# ahe_v1_0.net
KiCad netlist of a schematic drawn in EAGLE
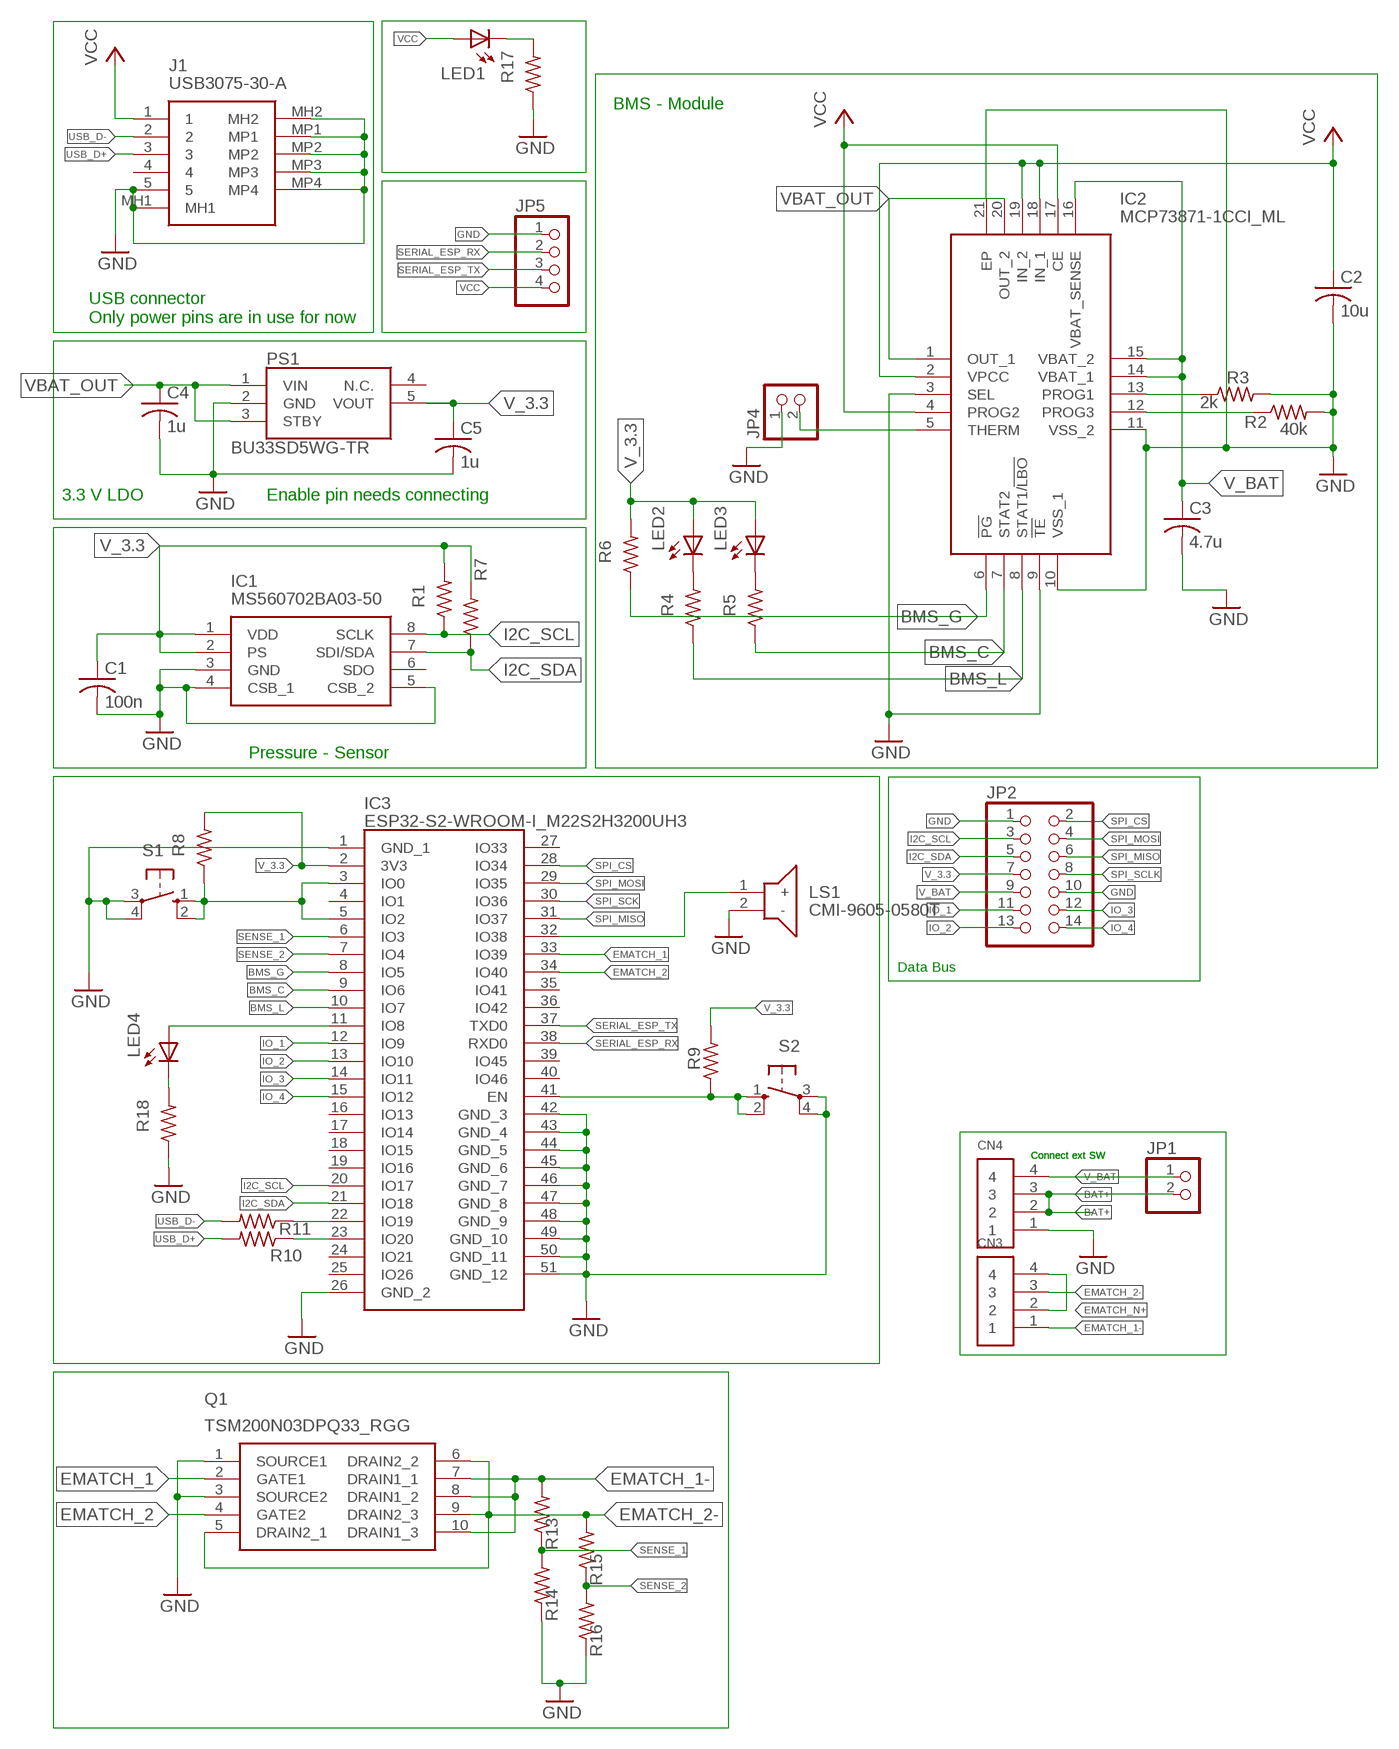
[diagram p0: schematic, sheet 1]

(export (version "E")
  (design (tool "Eeschema 10.0.6"))
  (components
    (comp (ref "C1")
      (value "100n")
      (footprint "eagle-import:C0805")
      (libsource (lib "eagle-import") (part "C-USC0805"))
    )
    (comp (ref "C2")
      (value "10u")
      (footprint "eagle-import:C0805")
      (libsource (lib "eagle-import") (part "C-USC0805"))
    )
    (comp (ref "C3")
      (value "4.7u")
      (footprint "eagle-import:C0805")
      (libsource (lib "eagle-import") (part "C-USC0805"))
    )
    (comp (ref "C4")
      (value "1u")
      (footprint "eagle-import:C0805")
      (libsource (lib "eagle-import") (part "C-USC0805"))
    )
    (comp (ref "C5")
      (value "1u")
      (footprint "eagle-import:C0805")
      (libsource (lib "eagle-import") (part "C-USC0805"))
    )
    (comp (ref "CN3")
      (value "1X4-3.5MM")
      (footprint "eagle-import:1X04-3.5MM")
      (libsource (lib "eagle-import") (part "1X4-3.5MM"))
    )
    (comp (ref "CN4")
      (value "1X4-3.5MM")
      (footprint "eagle-import:1X04-3.5MM")
      (libsource (lib "eagle-import") (part "1X4-3.5MM"))
    )
    (comp (ref "IC1")
      (value "MS560702BA03-50")
      (footprint "eagle-import:MS5607-02BA03")
      (fields (field (name "MOUSER_PART_NUMBER") "824-MS560702BA03-50"))
      (libsource (lib "eagle-import") (part "MS560702BA03-50"))
    )
    (comp (ref "IC2")
      (value "MCP73871-1CCI_ML")
      (footprint "eagle-import:QFN50P400X400X100-21N")
      (fields
        (field (name "MANUFACTURER_PART_NUMBER") "MCP73871-1CCI/ML")
        (field (name "MOUSER_PART_NUMBER") "579-MCP73871-1CCI/ML")
      )
      (libsource (lib "eagle-import") (part "MCP73871-1CCI_ML"))
    )
    (comp (ref "IC3")
      (value "ESP32-S2-WROOM-I_M22S2H3200UH3")
      (footprint "eagle-import:ESP32S2WROOMIM22S2H3200UH3Q0")
      (fields
        (field (name "MANUFACTURER_PART_NUMBER") "ESP32-S2-WROOM-I(M22S2H3200UH3Q0)")
        (field (name "MOUSER_PART_NUMBER") "356-ESP32S2WRMI320UH")
      )
      (libsource (lib "eagle-import") (part "ESP32-S2-WROOM-I_M22S2H3200UH3"))
    )
    (comp (ref "J1")
      (value "USB3075-30-A")
      (footprint "eagle-import:USB307530A")
      (fields (field (name "MOUSER_PART_NUMBER") "640-USB3075-30-A"))
      (libsource (lib "eagle-import") (part "USB3075-30-A"))
    )
    (comp (ref "JP1")
      (value "PINHD-1X2")
      (footprint "eagle-import:1X02")
      (libsource (lib "eagle-import") (part "PINHD-1X2"))
    )
    (comp (ref "JP2")
      (value "PINHD-2X7")
      (footprint "eagle-import:2X07")
      (libsource (lib "eagle-import") (part "PINHD-2X7"))
    )
    (comp (ref "JP4")
      (value "PINHD-1X2")
      (footprint "eagle-import:1X02")
      (libsource (lib "eagle-import") (part "PINHD-1X2"))
    )
    (comp (ref "JP5")
      (value "PINHD-1X4")
      (footprint "eagle-import:1X04")
      (libsource (lib "eagle-import") (part "PINHD-1X4"))
    )
    (comp (ref "LED1")
      (value "LEDCHIPLED_0805")
      (footprint "eagle-import:CHIPLED_0805")
      (libsource (lib "eagle-import") (part "LEDCHIPLED_0805"))
    )
    (comp (ref "LED2")
      (value "LEDCHIPLED_0805")
      (footprint "eagle-import:CHIPLED_0805")
      (libsource (lib "eagle-import") (part "LEDCHIPLED_0805"))
    )
    (comp (ref "LED3")
      (value "LEDCHIPLED_0805")
      (footprint "eagle-import:CHIPLED_0805")
      (libsource (lib "eagle-import") (part "LEDCHIPLED_0805"))
    )
    (comp (ref "LED4")
      (value "LEDCHIPLED_0805")
      (footprint "eagle-import:CHIPLED_0805")
      (libsource (lib "eagle-import") (part "LEDCHIPLED_0805"))
    )
    (comp (ref "LS1")
      (value "CMI-9605-0580T")
      (footprint "eagle-import:CMI96050580T")
      (fields (field (name "MOUSER_PART_NUMBER") "490-CMI-9605-0580T"))
      (libsource (lib "eagle-import") (part "CMI-9605-0580T"))
    )
    (comp (ref "PS1")
      (value "BU33SD5WG-TR")
      (footprint "eagle-import:SOT95P280X125-5N")
      (fields (field (name "MOUSER_PART_NUMBER") "755-BU33SD5WG-TR"))
      (libsource (lib "eagle-import") (part "BU33SD5WG-TR"))
    )
    (comp (ref "Q1")
      (value "TSM200N03DPQ33_RGG")
      (footprint "eagle-import:TSM200N03DPQ33RGG")
      (fields
        (field (name "MANUFACTURER_PART_NUMBER") "TSM200N03DPQ33 RGG")
        (field (name "MOUSER_PART_NUMBER") "821-TSM200N03DPQ33RG")
      )
      (libsource (lib "eagle-import") (part "TSM200N03DPQ33_RGG"))
    )
    (comp (ref "R1")
      (value "10k")
      (footprint "eagle-import:R0805")
      (libsource (lib "eagle-import") (part "R-US_R0805"))
    )
    (comp (ref "R2")
      (value "40k")
      (footprint "eagle-import:R0805")
      (libsource (lib "eagle-import") (part "R-US_R0805"))
    )
    (comp (ref "R3")
      (value "2k")
      (footprint "eagle-import:R0805")
      (libsource (lib "eagle-import") (part "R-US_R0805"))
    )
    (comp (ref "R4")
      (value "330")
      (footprint "eagle-import:R0805")
      (libsource (lib "eagle-import") (part "R-US_R0805"))
    )
    (comp (ref "R5")
      (value "330")
      (footprint "eagle-import:R0805")
      (libsource (lib "eagle-import") (part "R-US_R0805"))
    )
    (comp (ref "R6")
      (value "10k")
      (footprint "eagle-import:R0805")
      (libsource (lib "eagle-import") (part "R-US_R0805"))
    )
    (comp (ref "R7")
      (value "10k")
      (footprint "eagle-import:R0805")
      (libsource (lib "eagle-import") (part "R-US_R0805"))
    )
    (comp (ref "R8")
      (value "10k")
      (footprint "eagle-import:R0805")
      (libsource (lib "eagle-import") (part "R-US_R0805"))
    )
    (comp (ref "R9")
      (value "10k")
      (footprint "eagle-import:R0805")
      (libsource (lib "eagle-import") (part "R-US_R0805"))
    )
    (comp (ref "R10")
      (value "33")
      (footprint "eagle-import:R0805")
      (libsource (lib "eagle-import") (part "R-US_R0805"))
    )
    (comp (ref "R11")
      (value "33")
      (footprint "eagle-import:R0805")
      (libsource (lib "eagle-import") (part "R-US_R0805"))
    )
    (comp (ref "R13")
      (value "100k")
      (footprint "eagle-import:R0805")
      (libsource (lib "eagle-import") (part "R-US_R0805"))
    )
    (comp (ref "R14")
      (value "27k")
      (footprint "eagle-import:R0805")
      (libsource (lib "eagle-import") (part "R-US_R0805"))
    )
    (comp (ref "R15")
      (value "100k")
      (footprint "eagle-import:R0805")
      (libsource (lib "eagle-import") (part "R-US_R0805"))
    )
    (comp (ref "R16")
      (value "27k")
      (footprint "eagle-import:R0805")
      (libsource (lib "eagle-import") (part "R-US_R0805"))
    )
    (comp (ref "R17")
      (value "330")
      (footprint "eagle-import:R0805")
      (libsource (lib "eagle-import") (part "R-US_R0805"))
    )
    (comp (ref "R18")
      (value "330")
      (footprint "eagle-import:R0805")
      (libsource (lib "eagle-import") (part "R-US_R0805"))
    )
    (comp (ref "S1")
      (value "10-XX")
      (footprint "eagle-import:B3F-10XX")
      (fields (field (name "MPN") "B3F-1000"))
      (libsource (lib "eagle-import") (part "10-XX"))
    )
    (comp (ref "S2")
      (value "10-XX")
      (footprint "eagle-import:B3F-10XX")
      (fields (field (name "MPN") "B3F-1000"))
      (libsource (lib "eagle-import") (part "10-XX"))
    )
  )
  (nets
    (net (code "1") (name "BAT+") (class "Default")
      (node (ref "CN4") (pin "2") (pinfunction "2_2") (pintype "bidirectional"))
      (node (ref "CN4") (pin "3") (pinfunction "3_3") (pintype "bidirectional"))
      (node (ref "JP1") (pin "2") (pinfunction "2_2") (pintype "passive"))
    )
    (net (code "2") (name "BMS_C") (class "Default")
      (node (ref "IC2") (pin "7") (pinfunction "STAT2_7") (pintype "bidirectional"))
      (node (ref "IC3") (pin "9") (pinfunction "IO6_9") (pintype "bidirectional"))
      (node (ref "R5") (pin "1") (pinfunction "1_1") (pintype "passive"))
    )
    (net (code "3") (name "BMS_G") (class "Default")
      (node (ref "IC2") (pin "6") (pinfunction "~{PG}_6") (pintype "bidirectional"))
      (node (ref "IC3") (pin "8") (pinfunction "IO5_8") (pintype "bidirectional"))
      (node (ref "R6") (pin "1") (pinfunction "1_1") (pintype "passive"))
    )
    (net (code "4") (name "BMS_L") (class "Default")
      (node (ref "IC2") (pin "8") (pinfunction "STAT1/~{LBO}_8") (pintype "bidirectional"))
      (node (ref "IC3") (pin "10") (pinfunction "IO7_10") (pintype "bidirectional"))
      (node (ref "R4") (pin "1") (pinfunction "1_1") (pintype "passive"))
    )
    (net (code "5") (name "EMATCH_1") (class "Default")
      (node (ref "IC3") (pin "33") (pinfunction "IO39_33") (pintype "bidirectional"))
      (node (ref "Q1") (pin "2") (pinfunction "GATE1_2") (pintype "bidirectional"))
    )
    (net (code "6") (name "EMATCH_1-") (class "Default")
      (node (ref "CN3") (pin "1") (pinfunction "1_1") (pintype "bidirectional"))
      (node (ref "Q1") (pin "10") (pinfunction "DRAIN1_3_10") (pintype "bidirectional"))
      (node (ref "Q1") (pin "7") (pinfunction "DRAIN1_1_7") (pintype "bidirectional"))
      (node (ref "Q1") (pin "8") (pinfunction "DRAIN1_2_8") (pintype "bidirectional"))
      (node (ref "R13") (pin "2") (pinfunction "2_2") (pintype "passive"))
    )
    (net (code "7") (name "EMATCH_2") (class "Default")
      (node (ref "IC3") (pin "34") (pinfunction "IO40_34") (pintype "bidirectional"))
      (node (ref "Q1") (pin "4") (pinfunction "GATE2_4") (pintype "bidirectional"))
    )
    (net (code "8") (name "EMATCH_2-") (class "Default")
      (node (ref "CN3") (pin "3") (pinfunction "3_3") (pintype "bidirectional"))
      (node (ref "Q1") (pin "5") (pinfunction "DRAIN2_1_5") (pintype "bidirectional"))
      (node (ref "Q1") (pin "6") (pinfunction "DRAIN2_2_6") (pintype "bidirectional"))
      (node (ref "Q1") (pin "9") (pinfunction "DRAIN2_3_9") (pintype "bidirectional"))
      (node (ref "R15") (pin "2") (pinfunction "2_2") (pintype "passive"))
    )
    (net (code "9") (name "EMATCH_N+") (class "Default")
      (node (ref "CN3") (pin "2") (pinfunction "2_2") (pintype "bidirectional"))
      (node (ref "CN3") (pin "4") (pinfunction "4_4") (pintype "bidirectional"))
    )
    (net (code "10") (name "GND") (class "Default")
      (node (ref "C1") (pin "2") (pinfunction "2_2") (pintype "passive"))
      (node (ref "C2") (pin "2") (pinfunction "2_2") (pintype "passive"))
      (node (ref "C3") (pin "2") (pinfunction "2_2") (pintype "passive"))
      (node (ref "C4") (pin "2") (pinfunction "2_2") (pintype "passive"))
      (node (ref "C5") (pin "2") (pinfunction "2_2") (pintype "passive"))
      (node (ref "CN4") (pin "1") (pinfunction "1_1") (pintype "bidirectional"))
      (node (ref "IC1") (pin "3") (pinfunction "GND_3") (pintype "power_in"))
      (node (ref "IC1") (pin "4") (pinfunction "CSB_1_4") (pintype "input"))
      (node (ref "IC1") (pin "5") (pinfunction "CSB_2_5") (pintype "input"))
      (node (ref "IC2") (pin "10") (pinfunction "VSS_1_10") (pintype "bidirectional"))
      (node (ref "IC2") (pin "11") (pinfunction "VSS_2_11") (pintype "bidirectional"))
      (node (ref "IC2") (pin "21") (pinfunction "EP_21") (pintype "bidirectional"))
      (node (ref "IC2") (pin "3") (pinfunction "SEL_3") (pintype "bidirectional"))
      (node (ref "IC2") (pin "9") (pinfunction "~{TE}_9") (pintype "bidirectional"))
      (node (ref "IC3") (pin "1") (pinfunction "GND_1_1") (pintype "bidirectional"))
      (node (ref "IC3") (pin "26") (pinfunction "GND_2_26") (pintype "bidirectional"))
      (node (ref "IC3") (pin "42") (pinfunction "GND_3_42") (pintype "bidirectional"))
      (node (ref "IC3") (pin "43") (pinfunction "GND_4_43") (pintype "bidirectional"))
      (node (ref "IC3") (pin "44") (pinfunction "GND_5_44") (pintype "bidirectional"))
      (node (ref "IC3") (pin "45") (pinfunction "GND_6_45") (pintype "bidirectional"))
      (node (ref "IC3") (pin "46") (pinfunction "GND_7_46") (pintype "bidirectional"))
      (node (ref "IC3") (pin "47") (pinfunction "GND_8_47") (pintype "bidirectional"))
      (node (ref "IC3") (pin "48") (pinfunction "GND_9_48") (pintype "bidirectional"))
      (node (ref "IC3") (pin "49") (pinfunction "GND_10_49") (pintype "bidirectional"))
      (node (ref "IC3") (pin "50") (pinfunction "GND_11_50") (pintype "bidirectional"))
      (node (ref "IC3") (pin "51") (pinfunction "GND_12_51") (pintype "bidirectional"))
      (node (ref "J1") (pin "5") (pinfunction "5_5") (pintype "bidirectional"))
      (node (ref "J1") (pin "MH1") (pinfunction "MH1_MH1") (pintype "bidirectional"))
      (node (ref "J1") (pin "MH2") (pinfunction "MH2_MH2") (pintype "bidirectional"))
      (node (ref "J1") (pin "MP1") (pinfunction "MP1_MP1") (pintype "bidirectional"))
      (node (ref "J1") (pin "MP2") (pinfunction "MP2_MP2") (pintype "bidirectional"))
      (node (ref "J1") (pin "MP3") (pinfunction "MP3_MP3") (pintype "bidirectional"))
      (node (ref "J1") (pin "MP4") (pinfunction "MP4_MP4") (pintype "bidirectional"))
      (node (ref "JP2") (pin "1") (pinfunction "1_1") (pintype "passive"))
      (node (ref "JP2") (pin "10") (pinfunction "10_10") (pintype "passive"))
      (node (ref "JP4") (pin "1") (pinfunction "1_1") (pintype "passive"))
      (node (ref "JP5") (pin "1") (pinfunction "1_1") (pintype "passive"))
      (node (ref "LS1") (pin "2") (pinfunction "-_2") (pintype "bidirectional"))
      (node (ref "PS1") (pin "2") (pinfunction "GND_2") (pintype "bidirectional"))
      (node (ref "Q1") (pin "1") (pinfunction "SOURCE1_1") (pintype "bidirectional"))
      (node (ref "Q1") (pin "3") (pinfunction "SOURCE2_3") (pintype "bidirectional"))
      (node (ref "R14") (pin "1") (pinfunction "1_1") (pintype "passive"))
      (node (ref "R16") (pin "1") (pinfunction "1_1") (pintype "passive"))
      (node (ref "R17") (pin "1") (pinfunction "1_1") (pintype "passive"))
      (node (ref "R18") (pin "1") (pinfunction "1_1") (pintype "passive"))
      (node (ref "R2") (pin "2") (pinfunction "2_2") (pintype "passive"))
      (node (ref "R3") (pin "2") (pinfunction "2_2") (pintype "passive"))
      (node (ref "S1") (pin "3") (pinfunction "P_3") (pintype "passive"))
      (node (ref "S1") (pin "4") (pinfunction "P1_4") (pintype "passive"))
      (node (ref "S2") (pin "3") (pinfunction "P_3") (pintype "passive"))
      (node (ref "S2") (pin "4") (pinfunction "P1_4") (pintype "passive"))
    )
    (net (code "11") (name "I2C_SCL") (class "Default")
      (node (ref "IC1") (pin "8") (pinfunction "SCLK_8") (pintype "input"))
      (node (ref "IC3") (pin "20") (pinfunction "IO17_20") (pintype "bidirectional"))
      (node (ref "JP2") (pin "3") (pinfunction "3_3") (pintype "passive"))
      (node (ref "R1") (pin "1") (pinfunction "1_1") (pintype "passive"))
    )
    (net (code "12") (name "I2C_SDA") (class "Default")
      (node (ref "IC1") (pin "7") (pinfunction "SDI/SDA_7") (pintype "bidirectional"))
      (node (ref "IC3") (pin "21") (pinfunction "IO18_21") (pintype "bidirectional"))
      (node (ref "JP2") (pin "5") (pinfunction "5_5") (pintype "passive"))
      (node (ref "R7") (pin "1") (pinfunction "1_1") (pintype "passive"))
    )
    (net (code "13") (name "IO_1") (class "Default")
      (node (ref "IC3") (pin "12") (pinfunction "IO9_12") (pintype "bidirectional"))
      (node (ref "JP2") (pin "11") (pinfunction "11_11") (pintype "passive"))
    )
    (net (code "14") (name "IO_2") (class "Default")
      (node (ref "IC3") (pin "13") (pinfunction "IO10_13") (pintype "bidirectional"))
      (node (ref "JP2") (pin "13") (pinfunction "13_13") (pintype "passive"))
    )
    (net (code "15") (name "IO_3") (class "Default")
      (node (ref "IC3") (pin "14") (pinfunction "IO11_14") (pintype "bidirectional"))
      (node (ref "JP2") (pin "12") (pinfunction "12_12") (pintype "passive"))
    )
    (net (code "16") (name "IO_4") (class "Default")
      (node (ref "IC3") (pin "15") (pinfunction "IO12_15") (pintype "bidirectional"))
      (node (ref "JP2") (pin "14") (pinfunction "14_14") (pintype "passive"))
    )
    (net (code "17") (name "Net-(IC2-PROG1)") (class "Default")
      (node (ref "IC2") (pin "13") (pinfunction "PROG1_13") (pintype "bidirectional"))
      (node (ref "R3") (pin "1") (pinfunction "1_1") (pintype "passive"))
    )
    (net (code "18") (name "Net-(IC2-PROG3)") (class "Default")
      (node (ref "IC2") (pin "12") (pinfunction "PROG3_12") (pintype "bidirectional"))
      (node (ref "R2") (pin "1") (pinfunction "1_1") (pintype "passive"))
    )
    (net (code "19") (name "Net-(IC2-THERM)") (class "Default")
      (node (ref "IC2") (pin "5") (pinfunction "THERM_5") (pintype "bidirectional"))
      (node (ref "JP4") (pin "2") (pinfunction "2_2") (pintype "passive"))
    )
    (net (code "20") (name "Net-(IC3-EN)") (class "Default")
      (node (ref "IC3") (pin "41") (pinfunction "EN_41") (pintype "bidirectional"))
      (node (ref "R9") (pin "1") (pinfunction "1_1") (pintype "passive"))
      (node (ref "S2") (pin "1") (pinfunction "S_1") (pintype "passive"))
      (node (ref "S2") (pin "2") (pinfunction "S1_2") (pintype "passive"))
    )
    (net (code "21") (name "Net-(IC3-IO0)") (class "Default")
      (node (ref "IC3") (pin "3") (pinfunction "IO0_3") (pintype "bidirectional"))
      (node (ref "IC3") (pin "5") (pinfunction "IO2_5") (pintype "bidirectional"))
      (node (ref "R8") (pin "1") (pinfunction "1_1") (pintype "passive"))
      (node (ref "S1") (pin "1") (pinfunction "S_1") (pintype "passive"))
      (node (ref "S1") (pin "2") (pinfunction "S1_2") (pintype "passive"))
    )
    (net (code "22") (name "Net-(IC3-IO8)") (class "Default")
      (node (ref "IC3") (pin "11") (pinfunction "IO8_11") (pintype "bidirectional"))
      (node (ref "LED4") (pin "A") (pinfunction "A_A") (pintype "passive"))
    )
    (net (code "23") (name "Net-(IC3-IO19)") (class "Default")
      (node (ref "IC3") (pin "22") (pinfunction "IO19_22") (pintype "bidirectional"))
      (node (ref "R11") (pin "1") (pinfunction "1_1") (pintype "passive"))
    )
    (net (code "24") (name "Net-(IC3-IO20)") (class "Default")
      (node (ref "IC3") (pin "23") (pinfunction "IO20_23") (pintype "bidirectional"))
      (node (ref "R10") (pin "1") (pinfunction "1_1") (pintype "passive"))
    )
    (net (code "25") (name "Net-(IC3-IO38)") (class "Default")
      (node (ref "IC3") (pin "32") (pinfunction "IO38_32") (pintype "bidirectional"))
      (node (ref "LS1") (pin "1") (pinfunction "+_1") (pintype "bidirectional"))
    )
    (net (code "26") (name "Net-(LED1-PadC)") (class "Default")
      (node (ref "LED1") (pin "C") (pinfunction "C_C") (pintype "passive"))
      (node (ref "R17") (pin "2") (pinfunction "2_2") (pintype "passive"))
    )
    (net (code "27") (name "Net-(LED2-PadC)") (class "Default")
      (node (ref "LED2") (pin "C") (pinfunction "C_C") (pintype "passive"))
      (node (ref "R4") (pin "2") (pinfunction "2_2") (pintype "passive"))
    )
    (net (code "28") (name "Net-(LED3-PadC)") (class "Default")
      (node (ref "LED3") (pin "C") (pinfunction "C_C") (pintype "passive"))
      (node (ref "R5") (pin "2") (pinfunction "2_2") (pintype "passive"))
    )
    (net (code "29") (name "Net-(LED4-PadC)") (class "Default")
      (node (ref "LED4") (pin "C") (pinfunction "C_C") (pintype "passive"))
      (node (ref "R18") (pin "2") (pinfunction "2_2") (pintype "passive"))
    )
    (net (code "30") (name "SENSE_1") (class "Default")
      (node (ref "IC3") (pin "6") (pinfunction "IO3_6") (pintype "bidirectional"))
      (node (ref "R13") (pin "1") (pinfunction "1_1") (pintype "passive"))
      (node (ref "R14") (pin "2") (pinfunction "2_2") (pintype "passive"))
    )
    (net (code "31") (name "SENSE_2") (class "Default")
      (node (ref "IC3") (pin "7") (pinfunction "IO4_7") (pintype "bidirectional"))
      (node (ref "R15") (pin "1") (pinfunction "1_1") (pintype "passive"))
      (node (ref "R16") (pin "2") (pinfunction "2_2") (pintype "passive"))
    )
    (net (code "32") (name "SERIAL_ESP_RX") (class "Default")
      (node (ref "IC3") (pin "38") (pinfunction "RXD0_38") (pintype "bidirectional"))
      (node (ref "JP5") (pin "2") (pinfunction "2_2") (pintype "passive"))
    )
    (net (code "33") (name "SERIAL_ESP_TX") (class "Default")
      (node (ref "IC3") (pin "37") (pinfunction "TXD0_37") (pintype "bidirectional"))
      (node (ref "JP5") (pin "3") (pinfunction "3_3") (pintype "passive"))
    )
    (net (code "34") (name "SPI_CS") (class "Default")
      (node (ref "IC3") (pin "28") (pinfunction "IO34_28") (pintype "bidirectional"))
      (node (ref "JP2") (pin "2") (pinfunction "2_2") (pintype "passive"))
    )
    (net (code "35") (name "SPI_MISO") (class "Default")
      (node (ref "IC3") (pin "31") (pinfunction "IO37_31") (pintype "bidirectional"))
      (node (ref "JP2") (pin "6") (pinfunction "6_6") (pintype "passive"))
    )
    (net (code "36") (name "SPI_MOSI") (class "Default")
      (node (ref "IC3") (pin "29") (pinfunction "IO35_29") (pintype "bidirectional"))
      (node (ref "JP2") (pin "4") (pinfunction "4_4") (pintype "passive"))
    )
    (net (code "37") (name "SPI_SCK") (class "Default")
      (node (ref "IC3") (pin "30") (pinfunction "IO36_30") (pintype "bidirectional"))
    )
    (net (code "38") (name "SPI_SCLK") (class "Default")
      (node (ref "JP2") (pin "8") (pinfunction "8_8") (pintype "passive"))
    )
    (net (code "39") (name "USB_D+") (class "Default")
      (node (ref "J1") (pin "3") (pinfunction "3_3") (pintype "bidirectional"))
      (node (ref "R10") (pin "2") (pinfunction "2_2") (pintype "passive"))
    )
    (net (code "40") (name "USB_D-") (class "Default")
      (node (ref "J1") (pin "2") (pinfunction "2_2") (pintype "bidirectional"))
      (node (ref "R11") (pin "2") (pinfunction "2_2") (pintype "passive"))
    )
    (net (code "41") (name "VBAT_OUT") (class "Default")
      (node (ref "C4") (pin "1") (pinfunction "1_1") (pintype "passive"))
      (node (ref "IC2") (pin "1") (pinfunction "OUT_1_1") (pintype "bidirectional"))
      (node (ref "IC2") (pin "20") (pinfunction "OUT_2_20") (pintype "bidirectional"))
      (node (ref "PS1") (pin "1") (pinfunction "VIN_1") (pintype "bidirectional"))
      (node (ref "PS1") (pin "3") (pinfunction "STBY_3") (pintype "bidirectional"))
    )
    (net (code "42") (name "VCC") (class "Default")
      (node (ref "C2") (pin "1") (pinfunction "1_1") (pintype "passive"))
      (node (ref "IC2") (pin "17") (pinfunction "CE_17") (pintype "bidirectional"))
      (node (ref "IC2") (pin "18") (pinfunction "IN_1_18") (pintype "bidirectional"))
      (node (ref "IC2") (pin "19") (pinfunction "IN_2_19") (pintype "bidirectional"))
      (node (ref "IC2") (pin "2") (pinfunction "VPCC_2") (pintype "bidirectional"))
      (node (ref "IC2") (pin "4") (pinfunction "PROG2_4") (pintype "bidirectional"))
      (node (ref "J1") (pin "1") (pinfunction "1_1") (pintype "bidirectional"))
      (node (ref "JP5") (pin "4") (pinfunction "4_4") (pintype "passive"))
      (node (ref "LED1") (pin "A") (pinfunction "A_A") (pintype "passive"))
    )
    (net (code "43") (name "V_3.3") (class "Default")
      (node (ref "C1") (pin "1") (pinfunction "1_1") (pintype "passive"))
      (node (ref "C5") (pin "1") (pinfunction "1_1") (pintype "passive"))
      (node (ref "IC1") (pin "1") (pinfunction "VDD_1") (pintype "power_in"))
      (node (ref "IC1") (pin "2") (pinfunction "PS_2") (pintype "input"))
      (node (ref "IC3") (pin "2") (pinfunction "3V3_2") (pintype "bidirectional"))
      (node (ref "JP2") (pin "7") (pinfunction "7_7") (pintype "passive"))
      (node (ref "LED2") (pin "A") (pinfunction "A_A") (pintype "passive"))
      (node (ref "LED3") (pin "A") (pinfunction "A_A") (pintype "passive"))
      (node (ref "PS1") (pin "5") (pinfunction "VOUT_5") (pintype "bidirectional"))
      (node (ref "R1") (pin "2") (pinfunction "2_2") (pintype "passive"))
      (node (ref "R6") (pin "2") (pinfunction "2_2") (pintype "passive"))
      (node (ref "R7") (pin "2") (pinfunction "2_2") (pintype "passive"))
      (node (ref "R8") (pin "2") (pinfunction "2_2") (pintype "passive"))
      (node (ref "R9") (pin "2") (pinfunction "2_2") (pintype "passive"))
    )
    (net (code "44") (name "V_BAT") (class "Default")
      (node (ref "C3") (pin "1") (pinfunction "1_1") (pintype "passive"))
      (node (ref "CN4") (pin "4") (pinfunction "4_4") (pintype "bidirectional"))
      (node (ref "IC2") (pin "14") (pinfunction "VBAT_1_14") (pintype "bidirectional"))
      (node (ref "IC2") (pin "15") (pinfunction "VBAT_2_15") (pintype "bidirectional"))
      (node (ref "IC2") (pin "16") (pinfunction "VBAT_SENSE_16") (pintype "bidirectional"))
      (node (ref "JP1") (pin "1") (pinfunction "1_1") (pintype "passive"))
      (node (ref "JP2") (pin "9") (pinfunction "9_9") (pintype "passive"))
    )
    (net (code "45") (name "unconnected-(IC1-SDO-Pad6)") (class "Default")
      (node (ref "IC1") (pin "6") (pinfunction "SDO_6") (pintype "output"))
    )
    (net (code "46") (name "unconnected-(IC3-IO1-Pad4)") (class "Default")
      (node (ref "IC3") (pin "4") (pinfunction "IO1_4") (pintype "bidirectional"))
    )
    (net (code "47") (name "unconnected-(IC3-IO13-Pad16)") (class "Default")
      (node (ref "IC3") (pin "16") (pinfunction "IO13_16") (pintype "bidirectional"))
    )
    (net (code "48") (name "unconnected-(IC3-IO14-Pad17)") (class "Default")
      (node (ref "IC3") (pin "17") (pinfunction "IO14_17") (pintype "bidirectional"))
    )
    (net (code "49") (name "unconnected-(IC3-IO15-Pad18)") (class "Default")
      (node (ref "IC3") (pin "18") (pinfunction "IO15_18") (pintype "bidirectional"))
    )
    (net (code "50") (name "unconnected-(IC3-IO16-Pad19)") (class "Default")
      (node (ref "IC3") (pin "19") (pinfunction "IO16_19") (pintype "bidirectional"))
    )
    (net (code "51") (name "unconnected-(IC3-IO21-Pad24)") (class "Default")
      (node (ref "IC3") (pin "24") (pinfunction "IO21_24") (pintype "bidirectional"))
    )
    (net (code "52") (name "unconnected-(IC3-IO26-Pad25)") (class "Default")
      (node (ref "IC3") (pin "25") (pinfunction "IO26_25") (pintype "bidirectional"))
    )
    (net (code "53") (name "unconnected-(IC3-IO33-Pad27)") (class "Default")
      (node (ref "IC3") (pin "27") (pinfunction "IO33_27") (pintype "bidirectional"))
    )
    (net (code "54") (name "unconnected-(IC3-IO41-Pad35)") (class "Default")
      (node (ref "IC3") (pin "35") (pinfunction "IO41_35") (pintype "bidirectional"))
    )
    (net (code "55") (name "unconnected-(IC3-IO42-Pad36)") (class "Default")
      (node (ref "IC3") (pin "36") (pinfunction "IO42_36") (pintype "bidirectional"))
    )
    (net (code "56") (name "unconnected-(IC3-IO45-Pad39)") (class "Default")
      (node (ref "IC3") (pin "39") (pinfunction "IO45_39") (pintype "bidirectional"))
    )
    (net (code "57") (name "unconnected-(IC3-IO46-Pad40)") (class "Default")
      (node (ref "IC3") (pin "40") (pinfunction "IO46_40") (pintype "bidirectional"))
    )
    (net (code "58") (name "unconnected-(J1-Pad4)") (class "Default")
      (node (ref "J1") (pin "4") (pinfunction "4_4") (pintype "bidirectional"))
    )
    (net (code "59") (name "unconnected-(PS1-N.C.-Pad4)") (class "Default")
      (node (ref "PS1") (pin "4") (pinfunction "N.C._4") (pintype "no_connect"))
    )
  )
)
